# current_sense.net
KiCad netlist of a schematic drawn in Altium Designer
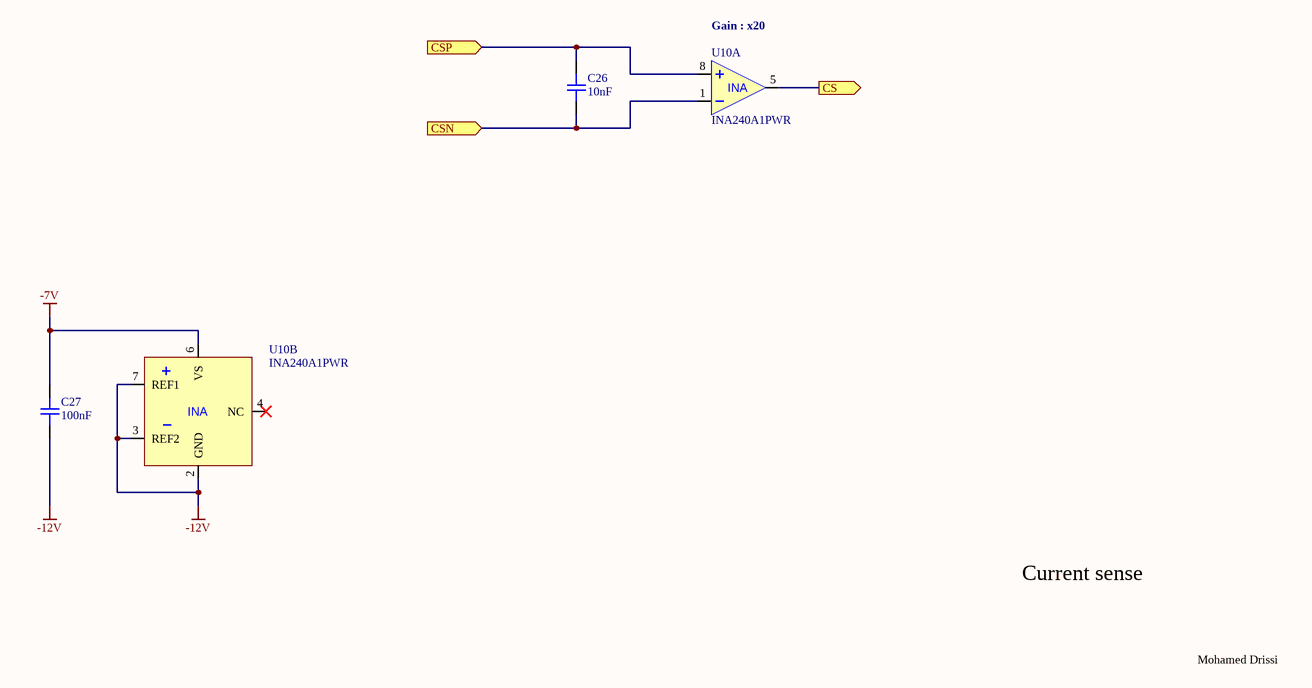
[diagram p0: current sense.SchDoc]

(export (version "E")
  (design (tool "Eeschema 10.0.6"))
  (components
    (comp (ref "C26")
      (value "C0603C103K4RACTU")
      (footprint "cap_0603")
      (description "Multilayer Ceramic Capacitors MLCC - SMD/SMT 16V 0.01uF X7R 0603 10%")
      (fields
        (field (name "MANUFACTURER") "Yageo Group")
        (field (name "TOLERANCE") "10%")
        (field (name "CAPACITANCE") "10nF")
      )
      (libsource (lib "Inverting buck boost") (part "Yageo C0603C103K4RACTU"))
    )
    (comp (ref "C27")
      (value "GMC10X7R104K100NT")
      (footprint "cap_0603")
      (description "100V 100nF X7R ±10% 0603 Multilayer Ceramic Capacitors MLCC - SMD/SMT ROHS")
      (fields (field (name "MANUFACTURER") "Cal-Chip Electronics") (field (name "CAPACITANCE") "100nF"))
      (libsource (lib "Inverting buck boost") (part "Cal-chip GMC10X7R104K100NT"))
    )
    (comp (ref "U10")
      (value "INA240A1PWR")
      (footprint "SOIC")
      (description "Op Amp Single Zero Drift Amplifier 5.5V 8-Pin TSSOP T/R")
      (fields (field (name "MANUFACTURER") "Texas Instruments"))
      (libsource (lib "Inverting buck boost") (part "TI INA240A1PWR"))
    )
  )
  (nets
    (net (code "1") (name "-7V") (class "Default")
      (node (ref "C27") (pin "2") (pinfunction "2_2") (pintype "passive"))
      (node (ref "U10") (pin "6") (pinfunction "VS_6") (pintype "passive"))
    )
    (net (code "2") (name "-12V") (class "Default")
      (node (ref "C27") (pin "1") (pinfunction "1_1") (pintype "passive"))
      (node (ref "U10") (pin "2") (pinfunction "GND_2") (pintype "passive"))
      (node (ref "U10") (pin "3") (pinfunction "REF2_3") (pintype "passive"))
      (node (ref "U10") (pin "7") (pinfunction "REF1_7") (pintype "passive"))
    )
    (net (code "3") (name "/CS") (class "Default")
      (node (ref "U10") (pin "5") (pinfunction "OUT_5") (pintype "passive"))
    )
    (net (code "4") (name "/CSN") (class "Default")
      (node (ref "C26") (pin "1") (pinfunction "1_1") (pintype "passive"))
      (node (ref "U10") (pin "1") (pinfunction "IN-_1") (pintype "passive"))
    )
    (net (code "5") (name "/CSP") (class "Default")
      (node (ref "C26") (pin "2") (pinfunction "2_2") (pintype "passive"))
      (node (ref "U10") (pin "8") (pinfunction "IN+_8") (pintype "passive"))
    )
    (net (code "6") (name "unconnected-(U10B-NC-Pad4)") (class "Default")
      (node (ref "U10") (pin "4") (pinfunction "NC_4") (pintype "passive+no_connect"))
    )
  )
)
